# LPEM.net
KiCad netlist of a schematic drawn in EAGLE
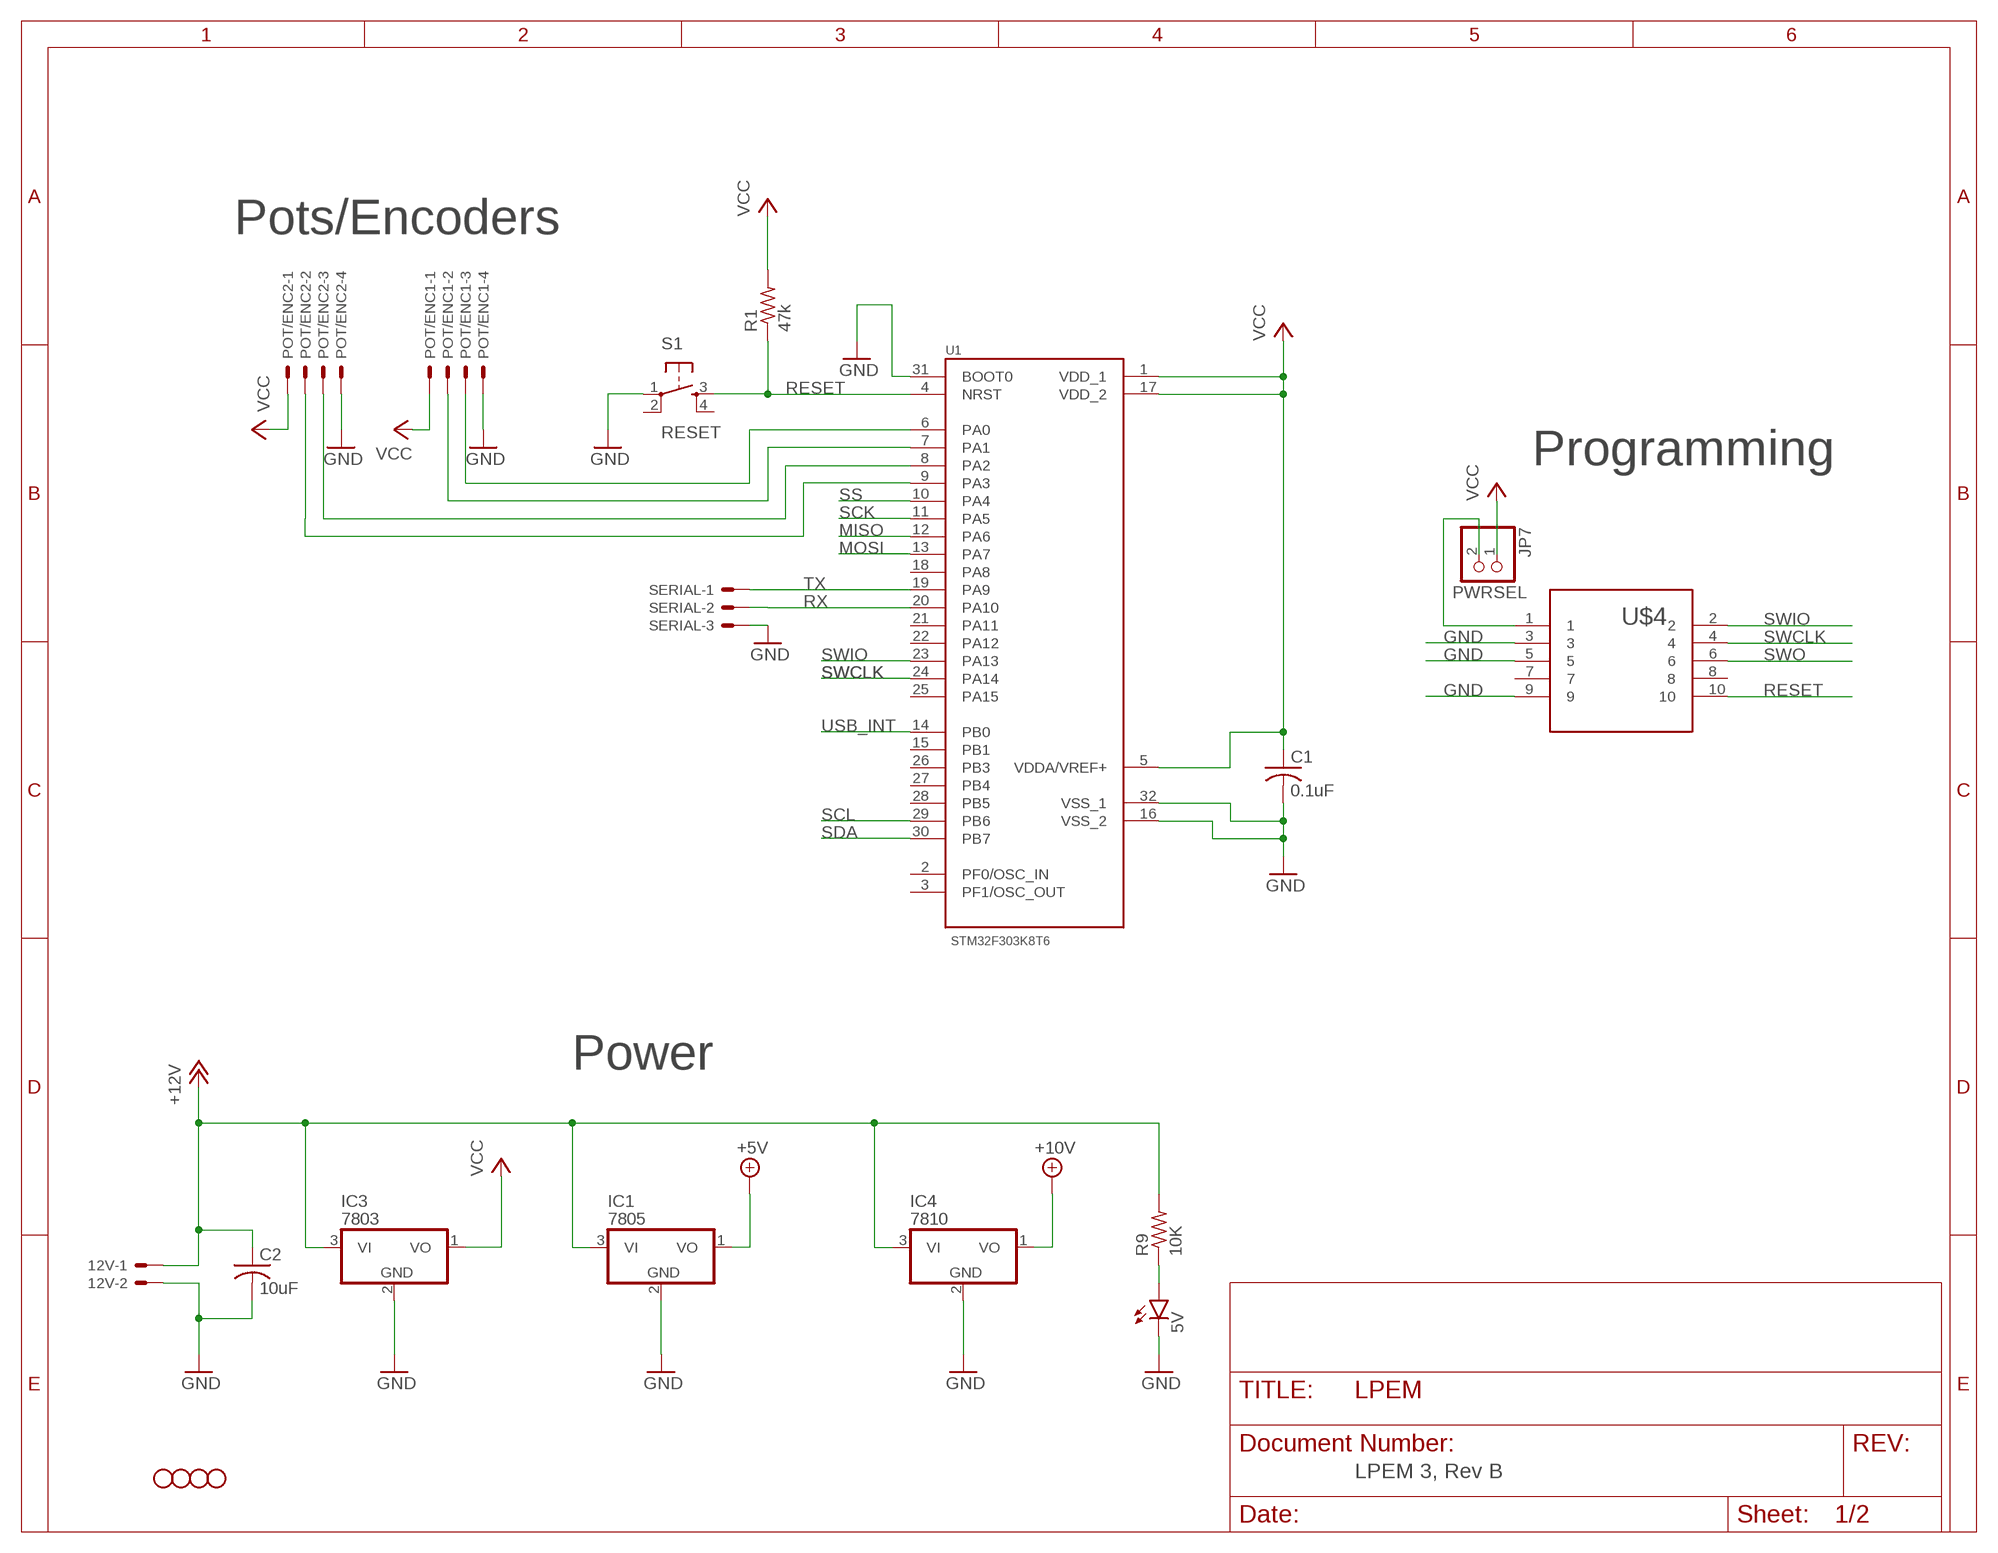
[diagram p0: schematic, sheet 1]
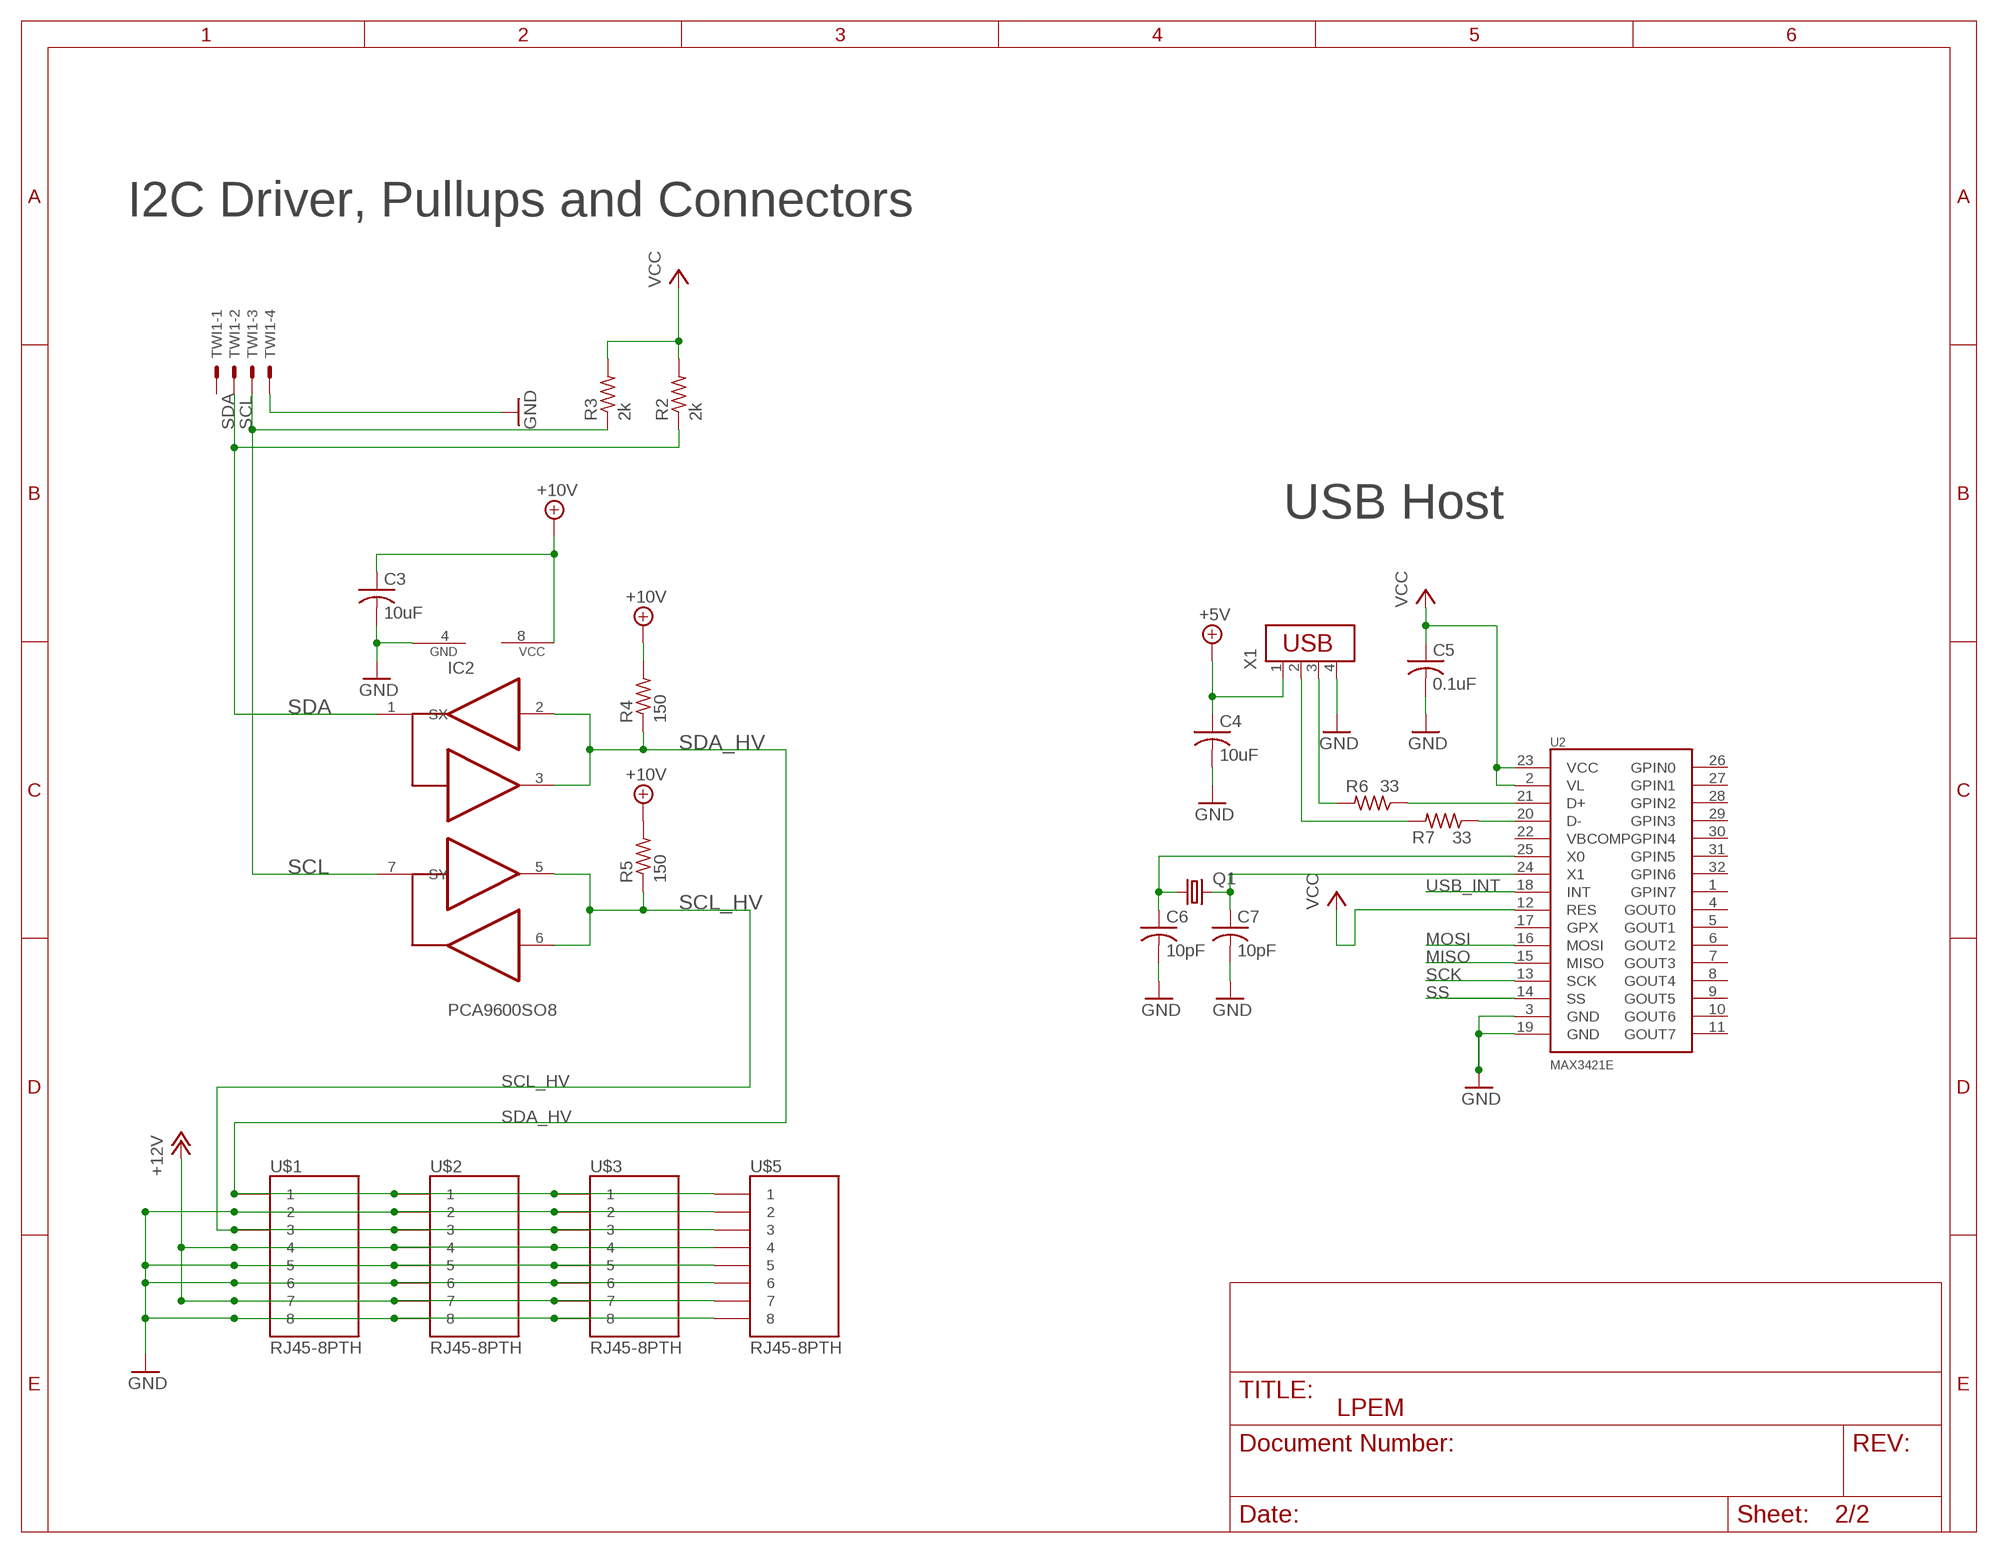
[diagram p1: schematic, sheet 2]

(export (version "E")
  (design (tool "Eeschema 10.0.6"))
  (components
    (comp (ref "C3")
      (value "10uF")
      (footprint "eagle-import:C025-025X050")
      (libsource (lib "eagle-import") (part "C-US025-025X050"))
    )
    (comp (ref "C4")
      (value "10uF")
      (footprint "eagle-import:C025-025X050")
      (libsource (lib "eagle-import") (part "C-US025-025X050"))
    )
    (comp (ref "C5")
      (value "0.1uF")
      (footprint "eagle-import:C025-025X050")
      (libsource (lib "eagle-import") (part "C-US025-025X050"))
    )
    (comp (ref "C6")
      (value "10pF")
      (footprint "eagle-import:C025-025X050")
      (libsource (lib "eagle-import") (part "C-US025-025X050"))
    )
    (comp (ref "C7")
      (value "10pF")
      (footprint "eagle-import:C025-025X050")
      (libsource (lib "eagle-import") (part "C-US025-025X050"))
    )
    (comp (ref "IC2")
      (value "PCA9600SO8")
      (footprint "eagle-import:SO08")
      (libsource (lib "eagle-import") (part "PCA9600SO8"))
    )
    (comp (ref "Q1")
      (value "CRYSTALHC18U-V")
      (footprint "eagle-import:HC18U-V")
      (libsource (lib "eagle-import") (part "CRYSTALHC18U-V"))
    )
    (comp (ref "R2")
      (value "2k")
      (footprint "eagle-import:0204_5")
      (libsource (lib "eagle-import") (part "R-US_0204/5"))
    )
    (comp (ref "R3")
      (value "2k")
      (footprint "eagle-import:0204_5")
      (libsource (lib "eagle-import") (part "R-US_0204/5"))
    )
    (comp (ref "R4")
      (value "150")
      (footprint "eagle-import:0204_5")
      (libsource (lib "eagle-import") (part "R-US_0204/5"))
    )
    (comp (ref "R5")
      (value "150")
      (footprint "eagle-import:0204_5")
      (libsource (lib "eagle-import") (part "R-US_0204/5"))
    )
    (comp (ref "R6")
      (value "33")
      (footprint "eagle-import:0204_5")
      (libsource (lib "eagle-import") (part "R-US_0204/5"))
    )
    (comp (ref "R7")
      (value "33")
      (footprint "eagle-import:0204_5")
      (libsource (lib "eagle-import") (part "R-US_0204/5"))
    )
    (comp (ref "TWI1")
      (value "22-23-2041")
      (footprint "eagle-import:22-23-2041")
      (fields (field (name "MF") "MOLEX"))
      (libsource (lib "eagle-import") (part "22-23-2041"))
    )
    (comp (ref "U$1")
      (value "RJ45-8PTH")
      (footprint "eagle-import:RJ45-8")
      (libsource (lib "eagle-import") (part "RJ45-8PTH"))
    )
    (comp (ref "U$2")
      (value "RJ45-8PTH")
      (footprint "eagle-import:RJ45-8")
      (libsource (lib "eagle-import") (part "RJ45-8PTH"))
    )
    (comp (ref "U$3")
      (value "RJ45-8PTH")
      (footprint "eagle-import:RJ45-8")
      (libsource (lib "eagle-import") (part "RJ45-8PTH"))
    )
    (comp (ref "U$5")
      (value "RJ45-8PTH")
      (footprint "eagle-import:RJ45-8")
      (libsource (lib "eagle-import") (part "RJ45-8PTH"))
    )
    (comp (ref "U2")
      (value "MAX3421E")
      (footprint "eagle-import:TQFP32-5MM")
      (fields (field (name "MF") "Maxim Integrated"))
      (libsource (lib "eagle-import") (part "MAX3421E"))
    )
    (comp (ref "X1")
      (value "USB-787616")
      (footprint "eagle-import:USB")
      (libsource (lib "eagle-import") (part "USB-787616"))
    )
    (comp (ref "5V")
      (value "LED3MM")
      (footprint "eagle-import:LED3MM")
      (libsource (lib "eagle-import") (part "LED3MM"))
    )
    (comp (ref "12V")
      (value "22-23-2021")
      (footprint "eagle-import:22-23-2021")
      (fields (field (name "MF") "MOLEX"))
      (libsource (lib "eagle-import") (part "22-23-2021"))
    )
    (comp (ref "C1")
      (value "0.1uF")
      (footprint "eagle-import:C025-025X050")
      (libsource (lib "eagle-import") (part "C-US025-025X050"))
    )
    (comp (ref "C2")
      (value "10uF")
      (footprint "eagle-import:C025-025X050")
      (libsource (lib "eagle-import") (part "C-US025-025X050"))
    )
    (comp (ref "IC1")
      (value "7805")
      (footprint "eagle-import:TO92")
      (libsource (lib "eagle-import") (part "78ZL05"))
    )
    (comp (ref "IC3")
      (value "7803")
      (footprint "eagle-import:TO92")
      (libsource (lib "eagle-import") (part "78ZL05"))
    )
    (comp (ref "IC4")
      (value "7810")
      (footprint "eagle-import:TO92")
      (libsource (lib "eagle-import") (part "78ZL05"))
    )
    (comp (ref "JP1")
      (value "STAND-OFF")
      (footprint "eagle-import:STAND-OFF")
      (libsource (lib "eagle-import") (part "STAND-OFF"))
    )
    (comp (ref "JP2")
      (value "STAND-OFF")
      (footprint "eagle-import:STAND-OFF")
      (libsource (lib "eagle-import") (part "STAND-OFF"))
    )
    (comp (ref "JP7")
      (value "PWRSEL")
      (footprint "eagle-import:1X02")
      (libsource (lib "eagle-import") (part "PINHD-1X2"))
    )
    (comp (ref "JP8")
      (value "STAND-OFF")
      (footprint "eagle-import:STAND-OFF")
      (libsource (lib "eagle-import") (part "STAND-OFF"))
    )
    (comp (ref "JP9")
      (value "STAND-OFF")
      (footprint "eagle-import:STAND-OFF")
      (libsource (lib "eagle-import") (part "STAND-OFF"))
    )
    (comp (ref "POT/ENC1")
      (value "22-23-2041")
      (footprint "eagle-import:22-23-2041")
      (fields (field (name "MF") "MOLEX"))
      (libsource (lib "eagle-import") (part "22-23-2041"))
    )
    (comp (ref "POT/ENC2")
      (value "22-23-2041")
      (footprint "eagle-import:22-23-2041")
      (fields (field (name "MF") "MOLEX"))
      (libsource (lib "eagle-import") (part "22-23-2041"))
    )
    (comp (ref "R1")
      (value "47k")
      (footprint "eagle-import:0204_5")
      (libsource (lib "eagle-import") (part "R-US_0204/5"))
    )
    (comp (ref "R9")
      (value "10K")
      (footprint "eagle-import:0204_5")
      (libsource (lib "eagle-import") (part "R-US_0204/5"))
    )
    (comp (ref "S1")
      (value "RESET")
      (footprint "eagle-import:TACTILE-PTH")
      (libsource (lib "eagle-import") (part "TAC_SWITCHPTH"))
    )
    (comp (ref "SERIAL")
      (value "22-23-2031")
      (footprint "eagle-import:22-23-2031")
      (fields (field (name "MF") "MOLEX"))
      (libsource (lib "eagle-import") (part "22-23-2031"))
    )
    (comp (ref "U$4")
      (value "CORTEX_HEADERJ")
      (footprint "eagle-import:CORTEX_HEADER")
      (fields (field (name "MF") "Samtec Inc.") (field (name "MP") "TFM-105-01-S-D-WT"))
      (libsource (lib "eagle-import") (part "CORTEX_HEADERJ"))
    )
    (comp (ref "U1")
      (value "STM32F303K8T6")
      (footprint "eagle-import:QFP80P900X900X160-32N")
      (fields (field (name "MF") "STMicroelectronics"))
      (libsource (lib "eagle-import") (part "STM32F303K8T6"))
    )
  )
  (nets
    (net (code "1") (name "+5V") (class "Default")
      (node (ref "C4") (pin "1") (pinfunction "1_1") (pintype "passive"))
      (node (ref "IC1") (pin "1") (pinfunction "VO_1") (pintype "passive"))
      (node (ref "X1") (pin "1") (pinfunction "1_1") (pintype "passive"))
    )
    (net (code "2") (name "+10V") (class "Default")
      (node (ref "C3") (pin "1") (pinfunction "1_1") (pintype "passive"))
      (node (ref "IC2") (pin "8") (pinfunction "VCC_8") (pintype "power_in"))
      (node (ref "IC4") (pin "1") (pinfunction "VO_1") (pintype "passive"))
      (node (ref "R4") (pin "2") (pinfunction "2_2") (pintype "passive"))
      (node (ref "R5") (pin "2") (pinfunction "2_2") (pintype "passive"))
    )
    (net (code "3") (name "+12V") (class "Default")
      (node (ref "12V") (pin "1") (pinfunction "S_1") (pintype "passive"))
      (node (ref "C2") (pin "1") (pinfunction "1_1") (pintype "passive"))
      (node (ref "IC1") (pin "3") (pinfunction "VI_3") (pintype "input"))
      (node (ref "IC3") (pin "3") (pinfunction "VI_3") (pintype "input"))
      (node (ref "IC4") (pin "3") (pinfunction "VI_3") (pintype "input"))
      (node (ref "R9") (pin "2") (pinfunction "2_2") (pintype "passive"))
      (node (ref "U$1") (pin "4") (pinfunction "4_4") (pintype "bidirectional"))
      (node (ref "U$1") (pin "7") (pinfunction "7_7") (pintype "bidirectional"))
      (node (ref "U$2") (pin "4") (pinfunction "4_4") (pintype "bidirectional"))
      (node (ref "U$2") (pin "7") (pinfunction "7_7") (pintype "bidirectional"))
      (node (ref "U$3") (pin "4") (pinfunction "4_4") (pintype "bidirectional"))
      (node (ref "U$3") (pin "7") (pinfunction "7_7") (pintype "bidirectional"))
      (node (ref "U$5") (pin "4") (pinfunction "4_4") (pintype "bidirectional"))
      (node (ref "U$5") (pin "7") (pinfunction "7_7") (pintype "bidirectional"))
    )
    (net (code "4") (name "GND") (class "Default")
      (node (ref "12V") (pin "2") (pinfunction "S_2") (pintype "passive"))
      (node (ref "5V") (pin "K") (pinfunction "C_K") (pintype "passive"))
      (node (ref "C1") (pin "2") (pinfunction "2_2") (pintype "passive"))
      (node (ref "C2") (pin "2") (pinfunction "2_2") (pintype "passive"))
      (node (ref "C3") (pin "2") (pinfunction "2_2") (pintype "passive"))
      (node (ref "C4") (pin "2") (pinfunction "2_2") (pintype "passive"))
      (node (ref "C5") (pin "2") (pinfunction "2_2") (pintype "passive"))
      (node (ref "C6") (pin "2") (pinfunction "2_2") (pintype "passive"))
      (node (ref "C7") (pin "2") (pinfunction "2_2") (pintype "passive"))
      (node (ref "IC1") (pin "2") (pinfunction "GND_2") (pintype "passive"))
      (node (ref "IC2") (pin "4") (pinfunction "GND_4") (pintype "power_in"))
      (node (ref "IC3") (pin "2") (pinfunction "GND_2") (pintype "passive"))
      (node (ref "IC4") (pin "2") (pinfunction "GND_2") (pintype "passive"))
      (node (ref "POT/ENC1") (pin "4") (pinfunction "S_4") (pintype "passive"))
      (node (ref "POT/ENC2") (pin "4") (pinfunction "S_4") (pintype "passive"))
      (node (ref "S1") (pin "1") (pinfunction "1_1") (pintype "passive"))
      (node (ref "SERIAL") (pin "3") (pinfunction "S_3") (pintype "passive"))
      (node (ref "TWI1") (pin "4") (pinfunction "S_4") (pintype "passive"))
      (node (ref "U$1") (pin "2") (pinfunction "2_2") (pintype "bidirectional"))
      (node (ref "U$1") (pin "5") (pinfunction "5_5") (pintype "bidirectional"))
      (node (ref "U$1") (pin "6") (pinfunction "6_6") (pintype "bidirectional"))
      (node (ref "U$1") (pin "8") (pinfunction "8_8") (pintype "bidirectional"))
      (node (ref "U$2") (pin "2") (pinfunction "2_2") (pintype "bidirectional"))
      (node (ref "U$2") (pin "5") (pinfunction "5_5") (pintype "bidirectional"))
      (node (ref "U$2") (pin "6") (pinfunction "6_6") (pintype "bidirectional"))
      (node (ref "U$2") (pin "8") (pinfunction "8_8") (pintype "bidirectional"))
      (node (ref "U$3") (pin "2") (pinfunction "2_2") (pintype "bidirectional"))
      (node (ref "U$3") (pin "5") (pinfunction "5_5") (pintype "bidirectional"))
      (node (ref "U$3") (pin "6") (pinfunction "6_6") (pintype "bidirectional"))
      (node (ref "U$3") (pin "8") (pinfunction "8_8") (pintype "bidirectional"))
      (node (ref "U$4") (pin "3") (pinfunction "3_3") (pintype "passive"))
      (node (ref "U$4") (pin "5") (pinfunction "5_5") (pintype "passive"))
      (node (ref "U$4") (pin "9") (pinfunction "9_9") (pintype "passive"))
      (node (ref "U$5") (pin "2") (pinfunction "2_2") (pintype "bidirectional"))
      (node (ref "U$5") (pin "5") (pinfunction "5_5") (pintype "bidirectional"))
      (node (ref "U$5") (pin "6") (pinfunction "6_6") (pintype "bidirectional"))
      (node (ref "U$5") (pin "8") (pinfunction "8_8") (pintype "bidirectional"))
      (node (ref "U1") (pin "16") (pinfunction "VSS_2_16") (pintype "power_in"))
      (node (ref "U1") (pin "31") (pinfunction "BOOT0_31") (pintype "input"))
      (node (ref "U1") (pin "32") (pinfunction "VSS_1_32") (pintype "power_in"))
      (node (ref "U2") (pin "19") (pinfunction "GND_19") (pintype "bidirectional"))
      (node (ref "U2") (pin "3") (pinfunction "GND_3") (pintype "bidirectional"))
      (node (ref "X1") (pin "4") (pinfunction "4_4") (pintype "passive"))
    )
    (net (code "5") (name "MISO") (class "Default")
      (node (ref "U1") (pin "12") (pinfunction "PA6_12") (pintype "bidirectional"))
      (node (ref "U2") (pin "15") (pinfunction "MISO_15") (pintype "bidirectional"))
    )
    (net (code "6") (name "MOSI") (class "Default")
      (node (ref "U1") (pin "13") (pinfunction "PA7_13") (pintype "bidirectional"))
      (node (ref "U2") (pin "16") (pinfunction "MOSI_16") (pintype "bidirectional"))
    )
    (net (code "7") (name "Net-(5V-PadA)") (class "Default")
      (node (ref "5V") (pin "A") (pinfunction "A_A") (pintype "passive"))
      (node (ref "R9") (pin "1") (pinfunction "1_1") (pintype "passive"))
    )
    (net (code "8") (name "Net-(JP7-Pad2)") (class "Default")
      (node (ref "JP7") (pin "2") (pinfunction "2_2") (pintype "passive"))
      (node (ref "U$4") (pin "1") (pinfunction "1_1") (pintype "passive"))
    )
    (net (code "9") (name "Net-(POT/ENC1B-S)") (class "Default")
      (node (ref "POT/ENC1") (pin "2") (pinfunction "S_2") (pintype "passive"))
      (node (ref "U1") (pin "7") (pinfunction "PA1_7") (pintype "bidirectional"))
    )
    (net (code "10") (name "Net-(POT/ENC1C-S)") (class "Default")
      (node (ref "POT/ENC1") (pin "3") (pinfunction "S_3") (pintype "passive"))
      (node (ref "U1") (pin "6") (pinfunction "PA0_6") (pintype "bidirectional"))
    )
    (net (code "11") (name "Net-(POT/ENC2B-S)") (class "Default")
      (node (ref "POT/ENC2") (pin "2") (pinfunction "S_2") (pintype "passive"))
      (node (ref "U1") (pin "9") (pinfunction "PA3_9") (pintype "bidirectional"))
    )
    (net (code "12") (name "Net-(POT/ENC2C-S)") (class "Default")
      (node (ref "POT/ENC2") (pin "3") (pinfunction "S_3") (pintype "passive"))
      (node (ref "U1") (pin "8") (pinfunction "PA2_8") (pintype "bidirectional"))
    )
    (net (code "13") (name "Net-(R6-Pad2)") (class "Default")
      (node (ref "R6") (pin "2") (pinfunction "2_2") (pintype "passive"))
      (node (ref "X1") (pin "3") (pinfunction "3_3") (pintype "passive"))
    )
    (net (code "14") (name "Net-(R7-Pad2)") (class "Default")
      (node (ref "R7") (pin "2") (pinfunction "2_2") (pintype "passive"))
      (node (ref "X1") (pin "2") (pinfunction "2_2") (pintype "passive"))
    )
    (net (code "15") (name "Net-(U2-D+)") (class "Default")
      (node (ref "R6") (pin "1") (pinfunction "1_1") (pintype "passive"))
      (node (ref "U2") (pin "21") (pinfunction "D+_21") (pintype "bidirectional"))
    )
    (net (code "16") (name "Net-(U2-D-)") (class "Default")
      (node (ref "R7") (pin "1") (pinfunction "1_1") (pintype "passive"))
      (node (ref "U2") (pin "20") (pinfunction "D-_20") (pintype "bidirectional"))
    )
    (net (code "17") (name "Net-(U2-X0)") (class "Default")
      (node (ref "C6") (pin "1") (pinfunction "1_1") (pintype "passive"))
      (node (ref "Q1") (pin "1") (pinfunction "1_1") (pintype "passive"))
      (node (ref "U2") (pin "25") (pinfunction "X0_25") (pintype "bidirectional"))
    )
    (net (code "18") (name "Net-(U2-X1)") (class "Default")
      (node (ref "C7") (pin "1") (pinfunction "1_1") (pintype "passive"))
      (node (ref "Q1") (pin "2") (pinfunction "2_2") (pintype "passive"))
      (node (ref "U2") (pin "24") (pinfunction "X1_24") (pintype "bidirectional"))
    )
    (net (code "19") (name "RESET") (class "Default")
      (node (ref "R1") (pin "1") (pinfunction "1_1") (pintype "passive"))
      (node (ref "S1") (pin "3") (pinfunction "3_3") (pintype "passive"))
      (node (ref "U$4") (pin "10") (pinfunction "10_10") (pintype "passive"))
      (node (ref "U1") (pin "4") (pinfunction "NRST_4") (pintype "bidirectional"))
    )
    (net (code "20") (name "RX") (class "Default")
      (node (ref "SERIAL") (pin "2") (pinfunction "S_2") (pintype "passive"))
      (node (ref "U1") (pin "20") (pinfunction "PA10_20") (pintype "bidirectional"))
    )
    (net (code "21") (name "SCK") (class "Default")
      (node (ref "U1") (pin "11") (pinfunction "PA5_11") (pintype "bidirectional"))
      (node (ref "U2") (pin "13") (pinfunction "SCK_13") (pintype "bidirectional"))
    )
    (net (code "22") (name "SCL") (class "Default")
      (node (ref "IC2") (pin "7") (pinfunction "SY_7") (pintype "bidirectional"))
      (node (ref "R3") (pin "1") (pinfunction "1_1") (pintype "passive"))
      (node (ref "TWI1") (pin "3") (pinfunction "S_3") (pintype "passive"))
      (node (ref "U1") (pin "29") (pinfunction "PB6_29") (pintype "bidirectional"))
    )
    (net (code "23") (name "SCL_HV") (class "Default")
      (node (ref "IC2") (pin "5") (pinfunction "TY_5") (pintype "output"))
      (node (ref "IC2") (pin "6") (pinfunction "RY_6") (pintype "input"))
      (node (ref "R5") (pin "1") (pinfunction "1_1") (pintype "passive"))
      (node (ref "U$1") (pin "3") (pinfunction "3_3") (pintype "bidirectional"))
      (node (ref "U$2") (pin "3") (pinfunction "3_3") (pintype "bidirectional"))
      (node (ref "U$3") (pin "3") (pinfunction "3_3") (pintype "bidirectional"))
      (node (ref "U$5") (pin "3") (pinfunction "3_3") (pintype "bidirectional"))
    )
    (net (code "24") (name "SDA") (class "Default")
      (node (ref "IC2") (pin "1") (pinfunction "SX_1") (pintype "bidirectional"))
      (node (ref "R2") (pin "1") (pinfunction "1_1") (pintype "passive"))
      (node (ref "TWI1") (pin "2") (pinfunction "S_2") (pintype "passive"))
      (node (ref "U1") (pin "30") (pinfunction "PB7_30") (pintype "bidirectional"))
    )
    (net (code "25") (name "SDA_HV") (class "Default")
      (node (ref "IC2") (pin "2") (pinfunction "RX_2") (pintype "input"))
      (node (ref "IC2") (pin "3") (pinfunction "TX_3") (pintype "output"))
      (node (ref "R4") (pin "1") (pinfunction "1_1") (pintype "passive"))
      (node (ref "U$1") (pin "1") (pinfunction "1_1") (pintype "bidirectional"))
      (node (ref "U$2") (pin "1") (pinfunction "1_1") (pintype "bidirectional"))
      (node (ref "U$3") (pin "1") (pinfunction "1_1") (pintype "bidirectional"))
      (node (ref "U$5") (pin "1") (pinfunction "1_1") (pintype "bidirectional"))
    )
    (net (code "26") (name "SS") (class "Default")
      (node (ref "U1") (pin "10") (pinfunction "PA4_10") (pintype "bidirectional"))
      (node (ref "U2") (pin "14") (pinfunction "SS_14") (pintype "bidirectional"))
    )
    (net (code "27") (name "SWCLK") (class "Default")
      (node (ref "U$4") (pin "4") (pinfunction "4_4") (pintype "passive"))
      (node (ref "U1") (pin "24") (pinfunction "PA14_24") (pintype "bidirectional"))
    )
    (net (code "28") (name "SWIO") (class "Default")
      (node (ref "U$4") (pin "2") (pinfunction "2_2") (pintype "passive"))
      (node (ref "U1") (pin "23") (pinfunction "PA13_23") (pintype "bidirectional"))
    )
    (net (code "29") (name "SWO") (class "Default")
      (node (ref "U$4") (pin "6") (pinfunction "6_6") (pintype "passive"))
    )
    (net (code "30") (name "TX") (class "Default")
      (node (ref "SERIAL") (pin "1") (pinfunction "S_1") (pintype "passive"))
      (node (ref "U1") (pin "19") (pinfunction "PA9_19") (pintype "bidirectional"))
    )
    (net (code "31") (name "USB_INT") (class "Default")
      (node (ref "U1") (pin "14") (pinfunction "PB0_14") (pintype "bidirectional"))
      (node (ref "U2") (pin "18") (pinfunction "INT_18") (pintype "bidirectional"))
    )
    (net (code "32") (name "VCC") (class "Default")
      (node (ref "C1") (pin "1") (pinfunction "1_1") (pintype "passive"))
      (node (ref "C5") (pin "1") (pinfunction "1_1") (pintype "passive"))
      (node (ref "IC3") (pin "1") (pinfunction "VO_1") (pintype "passive"))
      (node (ref "JP7") (pin "1") (pinfunction "1_1") (pintype "passive"))
      (node (ref "POT/ENC1") (pin "1") (pinfunction "S_1") (pintype "passive"))
      (node (ref "POT/ENC2") (pin "1") (pinfunction "S_1") (pintype "passive"))
      (node (ref "R1") (pin "2") (pinfunction "2_2") (pintype "passive"))
      (node (ref "R2") (pin "2") (pinfunction "2_2") (pintype "passive"))
      (node (ref "R3") (pin "2") (pinfunction "2_2") (pintype "passive"))
      (node (ref "U1") (pin "1") (pinfunction "VDD_1_1") (pintype "power_in"))
      (node (ref "U1") (pin "17") (pinfunction "VDD_2_17") (pintype "power_in"))
      (node (ref "U1") (pin "5") (pinfunction "VDDA/VREF+_5") (pintype "power_in"))
      (node (ref "U2") (pin "12") (pinfunction "RES_12") (pintype "bidirectional"))
      (node (ref "U2") (pin "2") (pinfunction "VL_2") (pintype "bidirectional"))
      (node (ref "U2") (pin "23") (pinfunction "VCC_23") (pintype "bidirectional"))
    )
    (net (code "33") (name "unconnected-(S1-Pad2)") (class "Default")
      (node (ref "S1") (pin "2") (pinfunction "2_2") (pintype "passive"))
    )
    (net (code "34") (name "unconnected-(S1-Pad4)") (class "Default")
      (node (ref "S1") (pin "4") (pinfunction "4_4") (pintype "passive"))
    )
    (net (code "35") (name "unconnected-(TWI1A-S-Pad1)") (class "Default")
      (node (ref "TWI1") (pin "1") (pinfunction "S_1") (pintype "passive"))
    )
    (net (code "36") (name "unconnected-(U$4-Pad7)") (class "Default")
      (node (ref "U$4") (pin "7") (pinfunction "7_7") (pintype "passive"))
    )
    (net (code "37") (name "unconnected-(U$4-Pad8)") (class "Default")
      (node (ref "U$4") (pin "8") (pinfunction "8_8") (pintype "passive"))
    )
    (net (code "38") (name "unconnected-(U1-PA8-Pad18)") (class "Default")
      (node (ref "U1") (pin "18") (pinfunction "PA8_18") (pintype "bidirectional"))
    )
    (net (code "39") (name "unconnected-(U1-PA11-Pad21)") (class "Default")
      (node (ref "U1") (pin "21") (pinfunction "PA11_21") (pintype "bidirectional"))
    )
    (net (code "40") (name "unconnected-(U1-PA12-Pad22)") (class "Default")
      (node (ref "U1") (pin "22") (pinfunction "PA12_22") (pintype "bidirectional"))
    )
    (net (code "41") (name "unconnected-(U1-PA15-Pad25)") (class "Default")
      (node (ref "U1") (pin "25") (pinfunction "PA15_25") (pintype "bidirectional"))
    )
    (net (code "42") (name "unconnected-(U1-PB1-Pad15)") (class "Default")
      (node (ref "U1") (pin "15") (pinfunction "PB1_15") (pintype "bidirectional"))
    )
    (net (code "43") (name "unconnected-(U1-PB3-Pad26)") (class "Default")
      (node (ref "U1") (pin "26") (pinfunction "PB3_26") (pintype "bidirectional"))
    )
    (net (code "44") (name "unconnected-(U1-PB4-Pad27)") (class "Default")
      (node (ref "U1") (pin "27") (pinfunction "PB4_27") (pintype "bidirectional"))
    )
    (net (code "45") (name "unconnected-(U1-PB5-Pad28)") (class "Default")
      (node (ref "U1") (pin "28") (pinfunction "PB5_28") (pintype "bidirectional"))
    )
    (net (code "46") (name "unconnected-(U1-PF0{slash}OSC_IN-Pad2)") (class "Default")
      (node (ref "U1") (pin "2") (pinfunction "PF0/OSC_IN_2") (pintype "bidirectional"))
    )
    (net (code "47") (name "unconnected-(U1-PF1{slash}OSC_OUT-Pad3)") (class "Default")
      (node (ref "U1") (pin "3") (pinfunction "PF1/OSC_OUT_3") (pintype "bidirectional"))
    )
    (net (code "48") (name "unconnected-(U2-GOUT0-Pad4)") (class "Default")
      (node (ref "U2") (pin "4") (pinfunction "GOUT0_4") (pintype "bidirectional"))
    )
    (net (code "49") (name "unconnected-(U2-GOUT1-Pad5)") (class "Default")
      (node (ref "U2") (pin "5") (pinfunction "GOUT1_5") (pintype "bidirectional"))
    )
    (net (code "50") (name "unconnected-(U2-GOUT2-Pad6)") (class "Default")
      (node (ref "U2") (pin "6") (pinfunction "GOUT2_6") (pintype "bidirectional"))
    )
    (net (code "51") (name "unconnected-(U2-GOUT3-Pad7)") (class "Default")
      (node (ref "U2") (pin "7") (pinfunction "GOUT3_7") (pintype "bidirectional"))
    )
    (net (code "52") (name "unconnected-(U2-GOUT4-Pad8)") (class "Default")
      (node (ref "U2") (pin "8") (pinfunction "GOUT4_8") (pintype "bidirectional"))
    )
    (net (code "53") (name "unconnected-(U2-GOUT5-Pad9)") (class "Default")
      (node (ref "U2") (pin "9") (pinfunction "GOUT5_9") (pintype "bidirectional"))
    )
    (net (code "54") (name "unconnected-(U2-GOUT6-Pad10)") (class "Default")
      (node (ref "U2") (pin "10") (pinfunction "GOUT6_10") (pintype "bidirectional"))
    )
    (net (code "55") (name "unconnected-(U2-GOUT7-Pad11)") (class "Default")
      (node (ref "U2") (pin "11") (pinfunction "GOUT7_11") (pintype "bidirectional"))
    )
    (net (code "56") (name "unconnected-(U2-GPIN0-Pad26)") (class "Default")
      (node (ref "U2") (pin "26") (pinfunction "GPIN0_26") (pintype "bidirectional"))
    )
    (net (code "57") (name "unconnected-(U2-GPIN1-Pad27)") (class "Default")
      (node (ref "U2") (pin "27") (pinfunction "GPIN1_27") (pintype "bidirectional"))
    )
    (net (code "58") (name "unconnected-(U2-GPIN2-Pad28)") (class "Default")
      (node (ref "U2") (pin "28") (pinfunction "GPIN2_28") (pintype "bidirectional"))
    )
    (net (code "59") (name "unconnected-(U2-GPIN3-Pad29)") (class "Default")
      (node (ref "U2") (pin "29") (pinfunction "GPIN3_29") (pintype "bidirectional"))
    )
    (net (code "60") (name "unconnected-(U2-GPIN4-Pad30)") (class "Default")
      (node (ref "U2") (pin "30") (pinfunction "GPIN4_30") (pintype "bidirectional"))
    )
    (net (code "61") (name "unconnected-(U2-GPIN5-Pad31)") (class "Default")
      (node (ref "U2") (pin "31") (pinfunction "GPIN5_31") (pintype "bidirectional"))
    )
    (net (code "62") (name "unconnected-(U2-GPIN6-Pad32)") (class "Default")
      (node (ref "U2") (pin "32") (pinfunction "GPIN6_32") (pintype "bidirectional"))
    )
    (net (code "63") (name "unconnected-(U2-GPIN7-Pad1)") (class "Default")
      (node (ref "U2") (pin "1") (pinfunction "GPIN7_1") (pintype "bidirectional"))
    )
    (net (code "64") (name "unconnected-(U2-GPX-Pad17)") (class "Default")
      (node (ref "U2") (pin "17") (pinfunction "GPX_17") (pintype "bidirectional"))
    )
    (net (code "65") (name "unconnected-(U2-VBCOMP-Pad22)") (class "Default")
      (node (ref "U2") (pin "22") (pinfunction "VBCOMP_22") (pintype "bidirectional"))
    )
  )
)
